# ValentinesFlower.net
KiCad netlist of a schematic drawn in Altium Designer
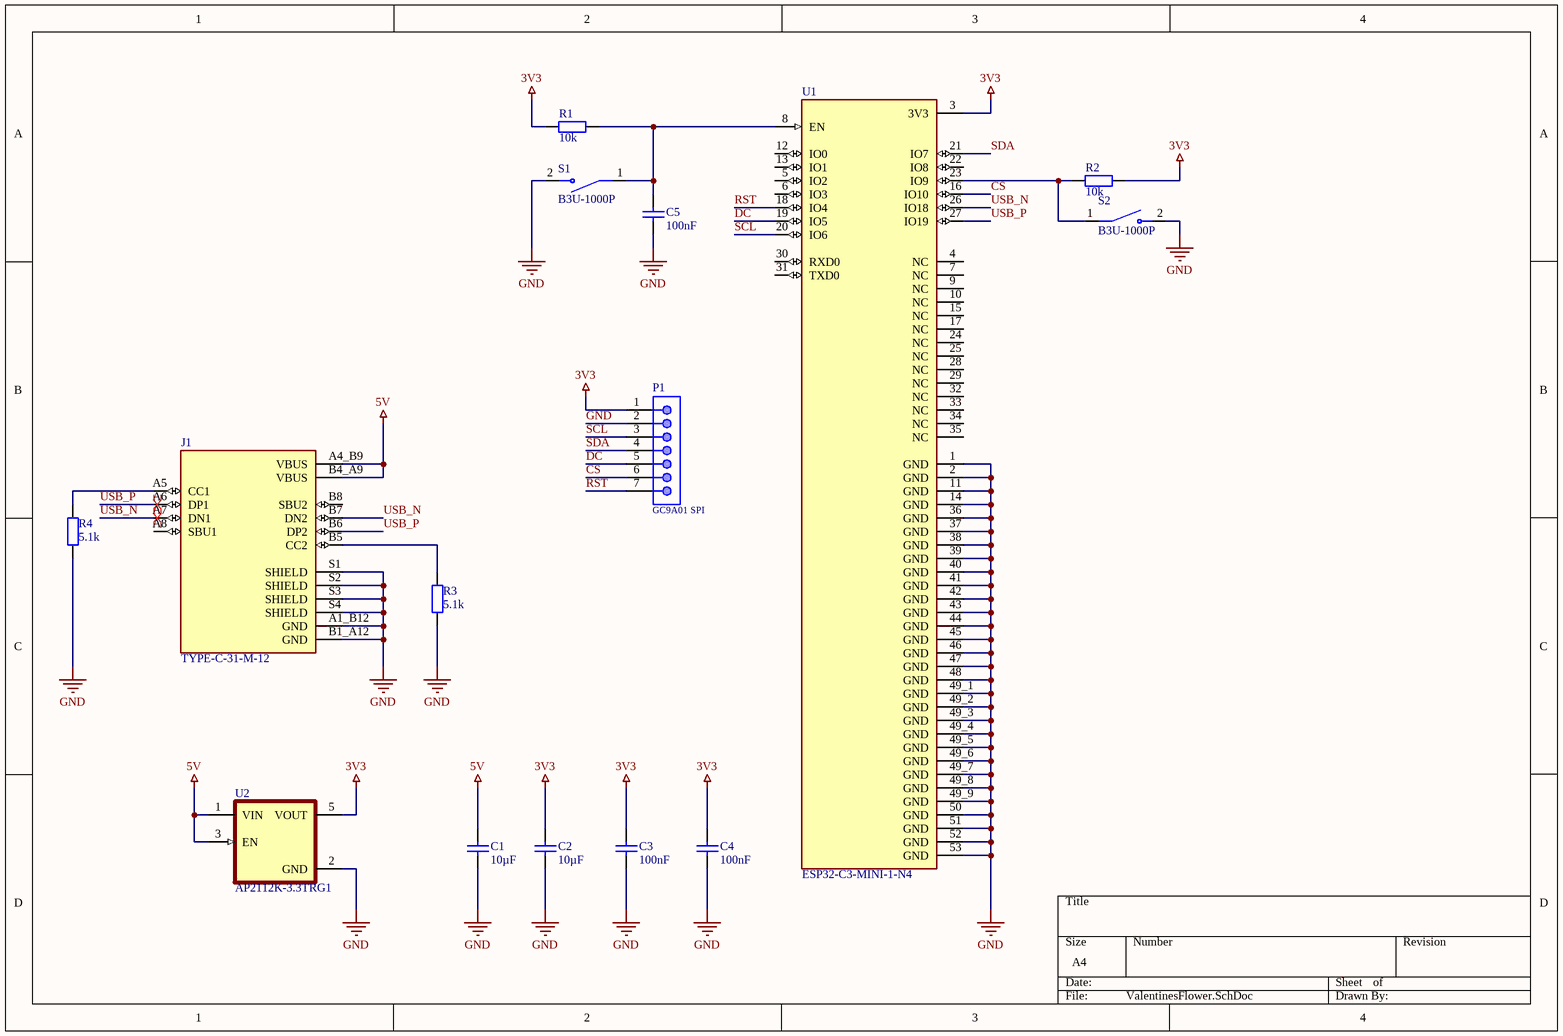
[diagram p0: ValentinesFlower.SchDoc]

(export (version "E")
  (design (tool "Eeschema 10.0.6"))
  (components
    (comp (ref "C1")
      (value "10µF")
      (footprint "WCAP-CSGP_0805_H=0.6mm_Reflow")
      (description "WCAP-CSGP General Purpose Ceramic Capacitors, size 0805, 220pF, +/-5%, 50VDC")
      (fields (field (name "PART NUMBER") "885012007059") (field (name "PUBLISHER") "Wurth Elektronik"))
      (libsource (lib "Altium_WCAP-CSGP (rev19a)") (part "885012007059"))
    )
    (comp (ref "C2")
      (value "10µF")
      (footprint "WCAP-CSGP_0805_H=0.6mm_Reflow")
      (description "WCAP-CSGP General Purpose Ceramic Capacitors, size 0805, 220pF, +/-5%, 50VDC")
      (fields (field (name "PART NUMBER") "885012007059") (field (name "PUBLISHER") "Wurth Elektronik"))
      (libsource (lib "Altium_WCAP-CSGP (rev19a)") (part "885012007059"))
    )
    (comp (ref "C3")
      (value "100nF")
      (footprint "WCAP-CSGP_0805_H=0.6mm_Reflow")
      (description "WCAP-CSGP General Purpose Ceramic Capacitors, size 0805, 220pF, +/-5%, 50VDC")
      (fields (field (name "PART NUMBER") "885012007059") (field (name "PUBLISHER") "Wurth Elektronik"))
      (libsource (lib "Altium_WCAP-CSGP (rev19a)") (part "885012007059"))
    )
    (comp (ref "C4")
      (value "100nF")
      (footprint "WCAP-CSGP_0805_H=0.6mm_Reflow")
      (description "WCAP-CSGP General Purpose Ceramic Capacitors, size 0805, 220pF, +/-5%, 50VDC")
      (fields (field (name "PART NUMBER") "885012007059") (field (name "PUBLISHER") "Wurth Elektronik"))
      (libsource (lib "Altium_WCAP-CSGP (rev19a)") (part "885012007059"))
    )
    (comp (ref "C5")
      (value "100nF")
      (footprint "WCAP-CSGP_0805_H=0.6mm_Reflow")
      (description "WCAP-CSGP General Purpose Ceramic Capacitors, size 0805, 220pF, +/-5%, 50VDC")
      (fields (field (name "PART NUMBER") "885012007059") (field (name "PUBLISHER") "Wurth Elektronik"))
      (libsource (lib "Altium_WCAP-CSGP (rev19a)") (part "885012007059"))
    )
    (comp (ref "J1")
      (value "TYPE-C-31-M-12")
      (footprint "HRO_TYPE-C-31-M-12")
      (description "USB Connectors 24 Receptacle 1 8.94*7.3mm RoHS")
      (fields (field (name "MF") "HRO Electronics Co., Ltd."))
      (libsource (lib "HRO_TYPE-C-31-M-12") (part "TYPE-C-31-M-12"))
    )
    (comp (ref "P1")
      (value "GC9A01 SPI")
      (footprint "61300711121")
      (description "WR-PHD Pin Header, THT, pitch 2.54mm, Single Row, Vertical, 7p")
      (fields
        (field (name "MANUFACTURER PART NUMBER") "61300711121")
        (field (name "MANUFACTURER") "Wurth Elektronik")
      )
      (libsource (lib "Altium_WR-PHD (rev20a)") (part "61300711121"))
    )
    (comp (ref "R1")
      (value "10k")
      (footprint "WRIS-PSMB_0805_H=0.35mm")
      (description "WRIS-PSMB Metal Plate Resistors, size 0805, 5mOhm, +/-1%, 0.5W")
      (fields (field (name "PART NUMBER") "580060720003") (field (name "PUBLISHER") "Wurth Elektronik"))
      (libsource (lib "") (part "580060720003_1"))
    )
    (comp (ref "R2")
      (value "10k")
      (footprint "WRIS-PSMB_0805_H=0.35mm")
      (description "WRIS-PSMB Metal Plate Resistors, size 0805, 5mOhm, +/-1%, 0.5W")
      (fields (field (name "PART NUMBER") "580060720003") (field (name "PUBLISHER") "Wurth Elektronik"))
      (libsource (lib "") (part "580060720003_1"))
    )
    (comp (ref "R3")
      (value "5.1k")
      (footprint "WRIS-PSMB_0805_H=0.35mm")
      (description "WRIS-PSMB Metal Plate Resistors, size 0805, 5mOhm, +/-1%, 0.5W")
      (fields (field (name "PART NUMBER") "580060720003") (field (name "PUBLISHER") "Wurth Elektronik"))
      (libsource (lib "Altium_WRIS-PSMB (rev19a)") (part "580060720003"))
    )
    (comp (ref "R4")
      (value "5.1k")
      (footprint "WRIS-PSMB_0805_H=0.35mm")
      (description "WRIS-PSMB Metal Plate Resistors, size 0805, 5mOhm, +/-1%, 0.5W")
      (fields (field (name "PART NUMBER") "580060720003") (field (name "PUBLISHER") "Wurth Elektronik"))
      (libsource (lib "Altium_WRIS-PSMB (rev19a)") (part "580060720003"))
    )
    (comp (ref "S1")
      (value "B3U-1000P")
      (footprint "OMRON_B3U-1000P_Switch:SW_B3U-1000P")
      (description "Switch Tactile N.O. SPST Round Button Gull Wing 0.05A 12VDC 1.5N SMD Embossed T/R")
      (libsource (lib "OMRON_B3U-1000P_Switch") (part "B3U-1000P"))
    )
    (comp (ref "S2")
      (value "B3U-1000P")
      (footprint "OMRON_B3U-1000P_Switch:SW_B3U-1000P")
      (description "Switch Tactile N.O. SPST Round Button Gull Wing 0.05A 12VDC 1.5N SMD Embossed T/R")
      (libsource (lib "OMRON_B3U-1000P_Switch") (part "B3U-1000P"))
    )
    (comp (ref "U1")
      (value "ESP32-C3-MINI-1-N4")
      (footprint "XCVR_ESP32-C3-MINI-1-N4")
      (fields (field (name "MF") "{'manufacturer': u'Espressif Systems'}"))
      (libsource (lib "ESP32-C3-MINI-1-N4") (part "ESP32-C3-MINI-1-N4"))
    )
    (comp (ref "U2")
      (value "AP2112K-3.3TRG1")
      (footprint "SOT95P285X140-5N")
      (description "Linear Voltage Regulator IC Positive Fixed 1 Output 600mA SOT-25")
      (fields (field (name "MF") "Diodes Inc."))
      (libsource (lib "AP2112K-3.3TRG1") (part "AP2112K-3.3TRG1"))
    )
  )
  (nets
    (net (code "1") (name "/CS") (class "Default")
      (node (ref "P1") (pin "6") (pinfunction "6_6") (pintype "passive"))
      (node (ref "U1") (pin "16") (pinfunction "IO10_16") (pintype "bidirectional"))
    )
    (net (code "2") (name "/DC") (class "Default")
      (node (ref "P1") (pin "5") (pinfunction "5_5") (pintype "passive"))
      (node (ref "U1") (pin "19") (pinfunction "IO5_19") (pintype "bidirectional"))
    )
    (net (code "3") (name "/RST") (class "Default")
      (node (ref "P1") (pin "7") (pinfunction "7_7") (pintype "passive"))
      (node (ref "U1") (pin "18") (pinfunction "IO4_18") (pintype "bidirectional"))
    )
    (net (code "4") (name "/SCL") (class "Default")
      (node (ref "P1") (pin "3") (pinfunction "3_3") (pintype "passive"))
      (node (ref "U1") (pin "20") (pinfunction "IO6_20") (pintype "bidirectional"))
    )
    (net (code "5") (name "/SDA") (class "Default")
      (node (ref "P1") (pin "4") (pinfunction "4_4") (pintype "passive"))
      (node (ref "U1") (pin "21") (pinfunction "IO7_21") (pintype "bidirectional"))
    )
    (net (code "6") (name "/USB_N") (class "Default")
      (node (ref "J1") (pin "A7") (pinfunction "DN1_A7") (pintype "bidirectional"))
      (node (ref "J1") (pin "B7") (pinfunction "DN2_B7") (pintype "bidirectional"))
      (node (ref "U1") (pin "26") (pinfunction "IO18_26") (pintype "bidirectional"))
    )
    (net (code "7") (name "/USB_P") (class "Default")
      (node (ref "J1") (pin "A6") (pinfunction "DP1_A6") (pintype "bidirectional"))
      (node (ref "J1") (pin "B6") (pinfunction "DP2_B6") (pintype "bidirectional"))
      (node (ref "U1") (pin "27") (pinfunction "IO19_27") (pintype "bidirectional"))
    )
    (net (code "8") (name "3V3") (class "Default")
      (node (ref "C2") (pin "2") (pinfunction "2_2") (pintype "passive"))
      (node (ref "C3") (pin "2") (pinfunction "2_2") (pintype "passive"))
      (node (ref "C4") (pin "2") (pinfunction "2_2") (pintype "passive"))
      (node (ref "P1") (pin "1") (pinfunction "1_1") (pintype "passive"))
      (node (ref "R1") (pin "1") (pinfunction "1_1") (pintype "passive"))
      (node (ref "R2") (pin "2") (pinfunction "2_2") (pintype "passive"))
      (node (ref "U1") (pin "3") (pinfunction "3V3_3") (pintype "power_in"))
      (node (ref "U2") (pin "5") (pinfunction "VOUT_5") (pintype "power_in"))
    )
    (net (code "9") (name "5V") (class "Default")
      (node (ref "C1") (pin "2") (pinfunction "2_2") (pintype "passive"))
      (node (ref "J1") (pin "A4_B9") (pinfunction "VBUS_A4_B9") (pintype "power_in"))
      (node (ref "J1") (pin "B4_A9") (pinfunction "VBUS_B4_A9") (pintype "power_in"))
      (node (ref "U2") (pin "1") (pinfunction "VIN_1") (pintype "power_in"))
      (node (ref "U2") (pin "3") (pinfunction "EN_3") (pintype "input"))
    )
    (net (code "10") (name "GND") (class "Default")
      (node (ref "C1") (pin "1") (pinfunction "1_1") (pintype "passive"))
      (node (ref "C2") (pin "1") (pinfunction "1_1") (pintype "passive"))
      (node (ref "C3") (pin "1") (pinfunction "1_1") (pintype "passive"))
      (node (ref "C4") (pin "1") (pinfunction "1_1") (pintype "passive"))
      (node (ref "C5") (pin "1") (pinfunction "1_1") (pintype "passive"))
      (node (ref "J1") (pin "A1_B12") (pinfunction "GND_A1_B12") (pintype "power_in"))
      (node (ref "J1") (pin "B1_A12") (pinfunction "GND_B1_A12") (pintype "power_in"))
      (node (ref "J1") (pin "S1") (pinfunction "SHIELD_S1") (pintype "passive"))
      (node (ref "J1") (pin "S2") (pinfunction "SHIELD_S2") (pintype "passive"))
      (node (ref "J1") (pin "S3") (pinfunction "SHIELD_S3") (pintype "passive"))
      (node (ref "J1") (pin "S4") (pinfunction "SHIELD_S4") (pintype "passive"))
      (node (ref "P1") (pin "2") (pinfunction "2_2") (pintype "passive"))
      (node (ref "R3") (pin "1") (pinfunction "1_1") (pintype "passive"))
      (node (ref "R4") (pin "1") (pinfunction "1_1") (pintype "passive"))
      (node (ref "S1") (pin "2") (pinfunction "2_2") (pintype "passive"))
      (node (ref "S2") (pin "2") (pinfunction "2_2") (pintype "passive"))
      (node (ref "U1") (pin "1") (pinfunction "GND_1") (pintype "power_in"))
      (node (ref "U1") (pin "11") (pinfunction "GND_11") (pintype "power_in"))
      (node (ref "U1") (pin "14") (pinfunction "GND_14") (pintype "power_in"))
      (node (ref "U1") (pin "2") (pinfunction "GND_2") (pintype "power_in"))
      (node (ref "U1") (pin "36") (pinfunction "GND_36") (pintype "power_in"))
      (node (ref "U1") (pin "37") (pinfunction "GND_37") (pintype "power_in"))
      (node (ref "U1") (pin "38") (pinfunction "GND_38") (pintype "power_in"))
      (node (ref "U1") (pin "39") (pinfunction "GND_39") (pintype "power_in"))
      (node (ref "U1") (pin "40") (pinfunction "GND_40") (pintype "power_in"))
      (node (ref "U1") (pin "41") (pinfunction "GND_41") (pintype "power_in"))
      (node (ref "U1") (pin "42") (pinfunction "GND_42") (pintype "power_in"))
      (node (ref "U1") (pin "43") (pinfunction "GND_43") (pintype "power_in"))
      (node (ref "U1") (pin "44") (pinfunction "GND_44") (pintype "power_in"))
      (node (ref "U1") (pin "45") (pinfunction "GND_45") (pintype "power_in"))
      (node (ref "U1") (pin "46") (pinfunction "GND_46") (pintype "power_in"))
      (node (ref "U1") (pin "47") (pinfunction "GND_47") (pintype "power_in"))
      (node (ref "U1") (pin "48") (pinfunction "GND_48") (pintype "power_in"))
      (node (ref "U1") (pin "49_1") (pinfunction "GND_49_1") (pintype "power_in"))
      (node (ref "U1") (pin "49_2") (pinfunction "GND_49_2") (pintype "power_in"))
      (node (ref "U1") (pin "49_3") (pinfunction "GND_49_3") (pintype "power_in"))
      (node (ref "U1") (pin "49_4") (pinfunction "GND_49_4") (pintype "power_in"))
      (node (ref "U1") (pin "49_5") (pinfunction "GND_49_5") (pintype "power_in"))
      (node (ref "U1") (pin "49_6") (pinfunction "GND_49_6") (pintype "power_in"))
      (node (ref "U1") (pin "49_7") (pinfunction "GND_49_7") (pintype "power_in"))
      (node (ref "U1") (pin "49_8") (pinfunction "GND_49_8") (pintype "power_in"))
      (node (ref "U1") (pin "49_9") (pinfunction "GND_49_9") (pintype "power_in"))
      (node (ref "U1") (pin "50") (pinfunction "GND_50") (pintype "power_in"))
      (node (ref "U1") (pin "51") (pinfunction "GND_51") (pintype "power_in"))
      (node (ref "U1") (pin "52") (pinfunction "GND_52") (pintype "power_in"))
      (node (ref "U1") (pin "53") (pinfunction "GND_53") (pintype "power_in"))
      (node (ref "U2") (pin "2") (pinfunction "GND_2") (pintype "power_in"))
    )
    (net (code "11") (name "Net-(J1-CC1)") (class "Default")
      (node (ref "J1") (pin "A5") (pinfunction "CC1_A5") (pintype "bidirectional"))
      (node (ref "R4") (pin "2") (pinfunction "2_2") (pintype "passive"))
    )
    (net (code "12") (name "Net-(J1-CC2)") (class "Default")
      (node (ref "J1") (pin "B5") (pinfunction "CC2_B5") (pintype "bidirectional"))
      (node (ref "R3") (pin "2") (pinfunction "2_2") (pintype "passive"))
    )
    (net (code "13") (name "Net-(U1-EN)") (class "Default")
      (node (ref "C5") (pin "2") (pinfunction "2_2") (pintype "passive"))
      (node (ref "R1") (pin "2") (pinfunction "2_2") (pintype "passive"))
      (node (ref "S1") (pin "1") (pinfunction "1_1") (pintype "passive"))
      (node (ref "U1") (pin "8") (pinfunction "EN_8") (pintype "input"))
    )
    (net (code "14") (name "Net-(U1-IO9)") (class "Default")
      (node (ref "R2") (pin "1") (pinfunction "1_1") (pintype "passive"))
      (node (ref "S2") (pin "1") (pinfunction "1_1") (pintype "passive"))
      (node (ref "U1") (pin "23") (pinfunction "IO9_23") (pintype "bidirectional"))
    )
    (net (code "15") (name "unconnected-(J1-SBU1-PadA8)") (class "Default")
      (node (ref "J1") (pin "A8") (pinfunction "SBU1_A8") (pintype "bidirectional"))
    )
    (net (code "16") (name "unconnected-(J1-SBU2-PadB8)") (class "Default")
      (node (ref "J1") (pin "B8") (pinfunction "SBU2_B8") (pintype "bidirectional"))
    )
    (net (code "17") (name "unconnected-(U1-IO0-Pad12)") (class "Default")
      (node (ref "U1") (pin "12") (pinfunction "IO0_12") (pintype "bidirectional"))
    )
    (net (code "18") (name "unconnected-(U1-IO1-Pad13)") (class "Default")
      (node (ref "U1") (pin "13") (pinfunction "IO1_13") (pintype "bidirectional"))
    )
    (net (code "19") (name "unconnected-(U1-IO2-Pad5)") (class "Default")
      (node (ref "U1") (pin "5") (pinfunction "IO2_5") (pintype "bidirectional"))
    )
    (net (code "20") (name "unconnected-(U1-IO3-Pad6)") (class "Default")
      (node (ref "U1") (pin "6") (pinfunction "IO3_6") (pintype "bidirectional"))
    )
    (net (code "21") (name "unconnected-(U1-IO8-Pad22)") (class "Default")
      (node (ref "U1") (pin "22") (pinfunction "IO8_22") (pintype "bidirectional"))
    )
    (net (code "22") (name "unconnected-(U1-NC-Pad4)") (class "Default")
      (node (ref "U1") (pin "4") (pinfunction "NC_4") (pintype "passive"))
    )
    (net (code "23") (name "unconnected-(U1-NC-Pad7)") (class "Default")
      (node (ref "U1") (pin "7") (pinfunction "NC_7") (pintype "passive"))
    )
    (net (code "24") (name "unconnected-(U1-NC-Pad9)") (class "Default")
      (node (ref "U1") (pin "9") (pinfunction "NC_9") (pintype "passive"))
    )
    (net (code "25") (name "unconnected-(U1-NC-Pad10)") (class "Default")
      (node (ref "U1") (pin "10") (pinfunction "NC_10") (pintype "passive"))
    )
    (net (code "26") (name "unconnected-(U1-NC-Pad15)") (class "Default")
      (node (ref "U1") (pin "15") (pinfunction "NC_15") (pintype "passive"))
    )
    (net (code "27") (name "unconnected-(U1-NC-Pad17)") (class "Default")
      (node (ref "U1") (pin "17") (pinfunction "NC_17") (pintype "passive"))
    )
    (net (code "28") (name "unconnected-(U1-NC-Pad24)") (class "Default")
      (node (ref "U1") (pin "24") (pinfunction "NC_24") (pintype "passive"))
    )
    (net (code "29") (name "unconnected-(U1-NC-Pad25)") (class "Default")
      (node (ref "U1") (pin "25") (pinfunction "NC_25") (pintype "passive"))
    )
    (net (code "30") (name "unconnected-(U1-NC-Pad28)") (class "Default")
      (node (ref "U1") (pin "28") (pinfunction "NC_28") (pintype "passive"))
    )
    (net (code "31") (name "unconnected-(U1-NC-Pad29)") (class "Default")
      (node (ref "U1") (pin "29") (pinfunction "NC_29") (pintype "passive"))
    )
    (net (code "32") (name "unconnected-(U1-NC-Pad32)") (class "Default")
      (node (ref "U1") (pin "32") (pinfunction "NC_32") (pintype "passive"))
    )
    (net (code "33") (name "unconnected-(U1-NC-Pad33)") (class "Default")
      (node (ref "U1") (pin "33") (pinfunction "NC_33") (pintype "passive"))
    )
    (net (code "34") (name "unconnected-(U1-NC-Pad34)") (class "Default")
      (node (ref "U1") (pin "34") (pinfunction "NC_34") (pintype "passive"))
    )
    (net (code "35") (name "unconnected-(U1-NC-Pad35)") (class "Default")
      (node (ref "U1") (pin "35") (pinfunction "NC_35") (pintype "passive"))
    )
    (net (code "36") (name "unconnected-(U1-RXD0-Pad30)") (class "Default")
      (node (ref "U1") (pin "30") (pinfunction "RXD0_30") (pintype "bidirectional"))
    )
    (net (code "37") (name "unconnected-(U1-TXD0-Pad31)") (class "Default")
      (node (ref "U1") (pin "31") (pinfunction "TXD0_31") (pintype "bidirectional"))
    )
  )
)
